# Amp_Stage.net
KiCad netlist of a schematic drawn in Altium Designer
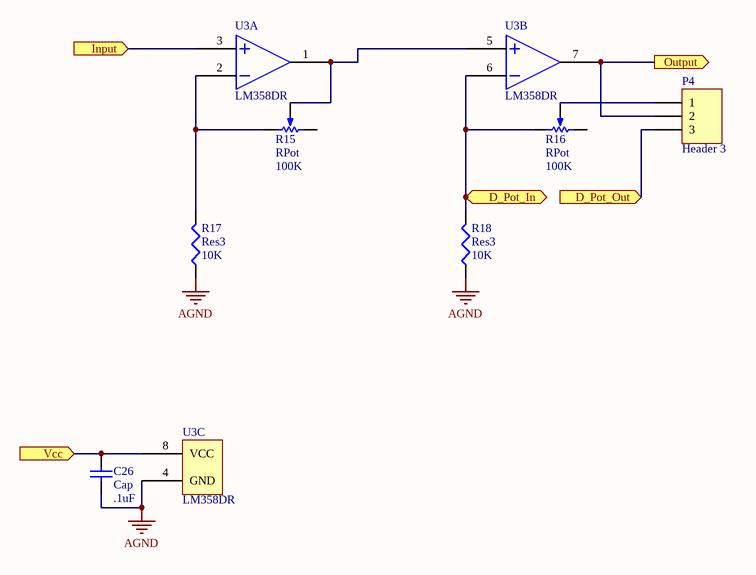
[diagram p0: Amp_Stage.SchDoc]

(export (version "E")
  (design (tool "Eeschema 10.0.6"))
  (components
    (comp (ref "C26")
      (value "Cap")
      (footprint "1608[0603]")
      (description "Capacitor")
      (fields (field (name "ALTIUM_VALUE") ".1uF") (field (name "PUBLISHER") "Altium Limited"))
      (libsource (lib "Miscellaneous Devices") (part "Cap"))
    )
    (comp (ref "P4")
      (value "Header 3")
      (footprint "HDR1X3")
      (description "Header, 3-Pin")
      (fields (field (name "PUBLISHER") "Altium Limited"))
      (libsource (lib "Miscellaneous Connectors") (part "Header 3"))
    )
    (comp (ref "R15")
      (value "RPot")
      (footprint "VR5")
      (description "Potentiometer")
      (fields (field (name "ALTIUM_VALUE") "100K") (field (name "PUBLISHER") "Altium Limited"))
      (libsource (lib "Miscellaneous Devices") (part "RPot"))
    )
    (comp (ref "R16")
      (value "RPot")
      (footprint "VR5")
      (description "Potentiometer")
      (fields (field (name "ALTIUM_VALUE") "100K") (field (name "PUBLISHER") "Altium Limited"))
      (libsource (lib "Miscellaneous Devices") (part "RPot"))
    )
    (comp (ref "R17")
      (value "Res3")
      (footprint "J1-0603")
      (description "Resistor")
      (fields (field (name "ALTIUM_VALUE") "10K") (field (name "PUBLISHER") "Altium Limited"))
      (libsource (lib "Miscellaneous Devices") (part "Res3"))
    )
    (comp (ref "R18")
      (value "Res3")
      (footprint "J1-0603")
      (description "Resistor")
      (fields (field (name "ALTIUM_VALUE") "10K") (field (name "PUBLISHER") "Altium Limited"))
      (libsource (lib "Miscellaneous Devices") (part "Res3"))
    )
    (comp (ref "U3")
      (value "LM358DR")
      (footprint "SOIC127P600X175-8N(lm358)")
      (libsource (lib "") (part "LM358DR_1"))
    )
  )
  (nets
    (net (code "1") (name "/D_Pot_In") (class "Default")
      (node (ref "R16") (pin "2") (pinfunction "BOT_2") (pintype "passive"))
      (node (ref "R18") (pin "2") (pinfunction "2_2") (pintype "passive"))
      (node (ref "U3") (pin "6") (pinfunction "2IN-_6") (pintype "passive"))
    )
    (net (code "2") (name "/D_Pot_Out") (class "Default")
      (node (ref "P4") (pin "3") (pinfunction "3_3") (pintype "passive"))
    )
    (net (code "3") (name "/Input") (class "Default")
      (node (ref "U3") (pin "3") (pinfunction "1IN+_3") (pintype "passive"))
    )
    (net (code "4") (name "/Output") (class "Default")
      (node (ref "P4") (pin "2") (pinfunction "2_2") (pintype "passive"))
      (node (ref "U3") (pin "7") (pinfunction "2OUT_7") (pintype "passive"))
    )
    (net (code "5") (name "/Vcc") (class "Default")
      (node (ref "C26") (pin "2") (pinfunction "2_2") (pintype "passive"))
      (node (ref "U3") (pin "8") (pinfunction "VCC_8") (pintype "passive"))
    )
    (net (code "6") (name "AGND") (class "Default")
      (node (ref "C26") (pin "1") (pinfunction "1_1") (pintype "passive"))
      (node (ref "R17") (pin "1") (pinfunction "1_1") (pintype "passive"))
      (node (ref "R18") (pin "1") (pinfunction "1_1") (pintype "passive"))
      (node (ref "U3") (pin "4") (pinfunction "GND_4") (pintype "passive"))
    )
    (net (code "7") (name "Net-(R15-BOT)") (class "Default")
      (node (ref "R15") (pin "2") (pinfunction "BOT_2") (pintype "passive"))
      (node (ref "R17") (pin "2") (pinfunction "2_2") (pintype "passive"))
      (node (ref "U3") (pin "2") (pinfunction "1IN-_2") (pintype "passive"))
    )
    (net (code "8") (name "Net-(R15-TAP)") (class "Default")
      (node (ref "R15") (pin "3") (pinfunction "TAP_3") (pintype "passive"))
      (node (ref "U3") (pin "1") (pinfunction "1OUT_1") (pintype "passive"))
      (node (ref "U3") (pin "5") (pinfunction "2IN+_5") (pintype "passive"))
    )
    (net (code "9") (name "Net-(R16-TAP)") (class "Default")
      (node (ref "P4") (pin "1") (pinfunction "1_1") (pintype "passive"))
      (node (ref "R16") (pin "3") (pinfunction "TAP_3") (pintype "passive"))
    )
    (net (code "10") (name "unconnected-(R15-TOP-Pad1)") (class "Default")
      (node (ref "R15") (pin "1") (pinfunction "TOP_1") (pintype "passive"))
    )
    (net (code "11") (name "unconnected-(R16-TOP-Pad1)") (class "Default")
      (node (ref "R16") (pin "1") (pinfunction "TOP_1") (pintype "passive"))
    )
  )
)
